# Sheet1.net
KiCad netlist of a schematic drawn in Altium Designer
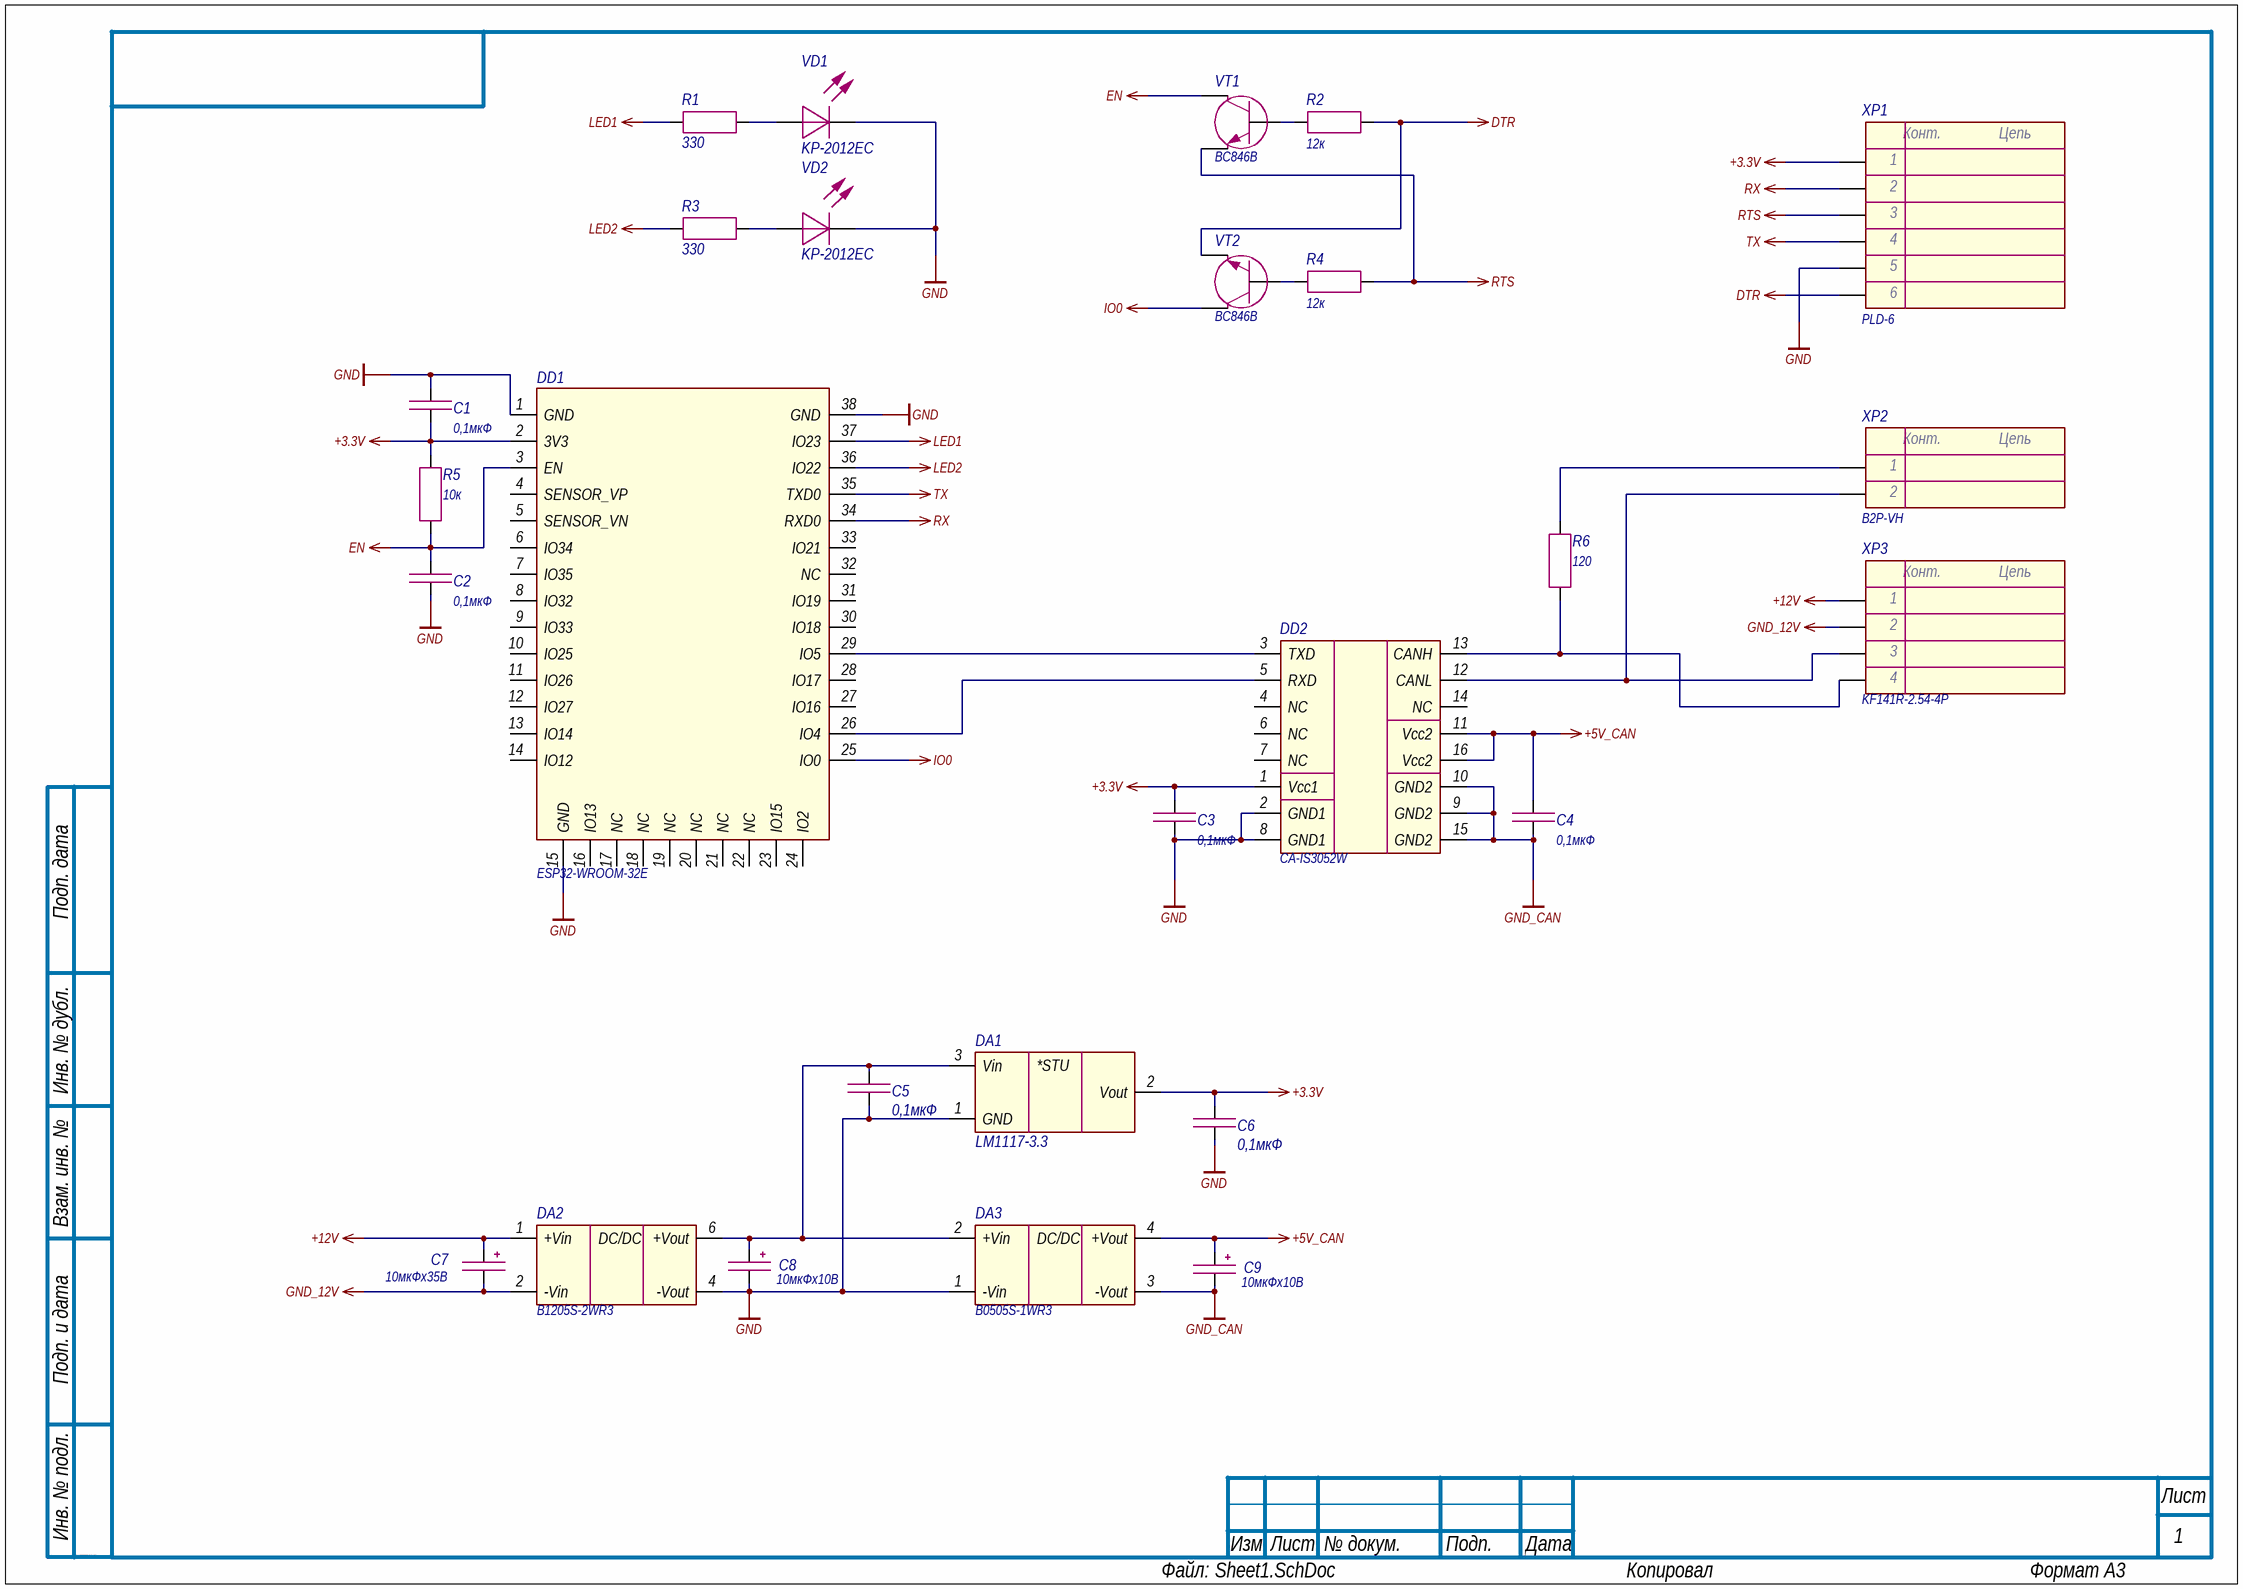
[diagram p0: Sheet1.SchDoc]

(export (version "E")
  (design (tool "Eeschema 10.0.6"))
  (components
    (comp (ref "C1")
      (value "0,1мкФ")
      (footprint "Pcb_library:CAP_0603")
      (fields (field (name "MANUFACTURER") "Murata"))
      (libsource (lib "lib") (part "Capacitor"))
    )
    (comp (ref "C2")
      (value "0,1мкФ")
      (footprint "Pcb_library:CAP_0603")
      (fields (field (name "MANUFACTURER") "Murata"))
      (libsource (lib "lib") (part "Capacitor"))
    )
    (comp (ref "C3")
      (value "0,1мкФ")
      (footprint "Pcb_library:CAP_0603")
      (fields (field (name "MANUFACTURER") "Murata"))
      (libsource (lib "lib") (part "Capacitor"))
    )
    (comp (ref "C4")
      (value "0,1мкФ")
      (footprint "Pcb_library:CAP_0603")
      (fields (field (name "MANUFACTURER") "Murata"))
      (libsource (lib "lib") (part "Capacitor"))
    )
    (comp (ref "C5")
      (value "0,1мкФ")
      (footprint "Pcb_library:CAP_0603")
      (fields (field (name "MANUFACTURER") "Murata"))
      (libsource (lib "lib") (part "Capacitor"))
    )
    (comp (ref "C6")
      (value "0,1мкФ")
      (footprint "Pcb_library:CAP_0603")
      (fields (field (name "MANUFACTURER") "Murata"))
      (libsource (lib "lib") (part "Capacitor"))
    )
    (comp (ref "C7")
      (value "10мкФх35B")
      (footprint "Pcb_library:CAP_C")
      (libsource (lib "Schem_library") (part "Capacitor_Polar"))
    )
    (comp (ref "C8")
      (value "10мкФх10B")
      (footprint "Pcb_library:CAP_A")
      (libsource (lib "Schem_library") (part "Capacitor_Polar"))
    )
    (comp (ref "C9")
      (value "10мкФх10B")
      (footprint "Pcb_library:CAP_A")
      (libsource (lib "Schem_library") (part "Capacitor_Polar"))
    )
    (comp (ref "DA1")
      (value "LM1117-3.3")
      (footprint "Pcb_library:TO-252")
      (fields (field (name "MANUFACTURER") "STMicroelectronics"))
      (libsource (lib "lib") (part "LM1117-3.3"))
    )
    (comp (ref "DA2")
      (value "B1205S-2WR3")
      (footprint "PcbLib1:B1205S2WR3")
      (description "Power Supply")
      (libsource (lib "Schlib1") (part "B1205S-2WR3"))
    )
    (comp (ref "DA3")
      (value "B0505S-1WR3")
      (footprint "B0505S1WR3")
      (description "Power Supply")
      (libsource (lib "Schlib1") (part "B0505S-1WR3"))
    )
    (comp (ref "DD1")
      (value "ESP32-WROOM-32E")
      (footprint "ESP32_WROOM_32E")
      (libsource (lib "lib") (part "ESP32-WROOM-32E"))
    )
    (comp (ref "DD2")
      (value "CA-IS3052W")
      (footprint "SOIC-16W")
      (description "Isolated CAN Transceiver")
      (libsource (lib "lib") (part "CA-IS3052W"))
    )
    (comp (ref "R1")
      (value "330")
      (footprint "Pcb_library:RES_0603")
      (fields (field (name "MANUFACTURER") "Yageo"))
      (libsource (lib "lib") (part "Resistor_6"))
    )
    (comp (ref "R2")
      (value "12к")
      (footprint "Pcb_library:RES_0603")
      (fields (field (name "MANUFACTURER") "Yageo"))
      (libsource (lib "lib") (part "Resistor_14"))
    )
    (comp (ref "R3")
      (value "330")
      (footprint "Pcb_library:RES_0603")
      (fields (field (name "MANUFACTURER") "Yageo"))
      (libsource (lib "lib") (part "Resistor_6"))
    )
    (comp (ref "R4")
      (value "12к")
      (footprint "Pcb_library:RES_0603")
      (fields (field (name "MANUFACTURER") "Yageo"))
      (libsource (lib "lib") (part "Resistor_14"))
    )
    (comp (ref "R5")
      (value "10к")
      (footprint "Pcb_library:RES_0603")
      (fields (field (name "MANUFACTURER") "Yageo"))
      (libsource (lib "lib") (part "Resistor_1"))
    )
    (comp (ref "R6")
      (value "120")
      (footprint "Pcb_library:RES_0805")
      (fields (field (name "MANUFACTURER") "Yageo"))
      (libsource (lib "lib") (part "Resistor_5"))
    )
    (comp (ref "VD1")
      (value "KP-2012EC")
      (footprint "Pcb_library:LED_0805")
      (fields (field (name "MANUFACTURER") "Kingbright"))
      (libsource (lib "lib") (part "LED"))
    )
    (comp (ref "VD2")
      (value "KP-2012EC")
      (footprint "Pcb_library:LED_0805")
      (fields (field (name "MANUFACTURER") "Kingbright"))
      (libsource (lib "lib") (part "LED"))
    )
    (comp (ref "VT1")
      (value "BC846B")
      (footprint "SOT-23-3")
      (description "npn")
      (libsource (lib "lib") (part "BC846B"))
    )
    (comp (ref "VT2")
      (value "BC846B")
      (footprint "SOT-23-3")
      (description "npn")
      (libsource (lib "lib") (part "BC846B"))
    )
    (comp (ref "XP1")
      (value "PLD-6")
      (footprint "Pcb_library:PLD-6")
      (fields (field (name "MANUFACTURER") "Connfly"))
      (libsource (lib "lib") (part "Connector-6"))
    )
    (comp (ref "XP2")
      (value "B2P-VH")
      (footprint "HDR-TH_2P-P2.54-V-M")
      (fields (field (name "MANUFACTURER") "JST"))
      (libsource (lib "lib") (part "Connector-2"))
    )
    (comp (ref "XP3")
      (value "KF141R-2.54-4P")
      (footprint "CONN-TH_4P-P2.54_KF141R-2.54-4P")
      (libsource (lib "Schlib1") (part "KF141R-2.54-4P"))
    )
  )
  (nets
    (net (code "1") (name "+3.3V") (class "Default")
      (node (ref "C1") (pin "1") (pinfunction "1_1") (pintype "passive"))
      (node (ref "C3") (pin "2") (pinfunction "2_2") (pintype "passive"))
      (node (ref "C6") (pin "2") (pinfunction "2_2") (pintype "passive"))
      (node (ref "DA1") (pin "2") (pinfunction "Vout_2") (pintype "passive"))
      (node (ref "DD1") (pin "2") (pinfunction "3V3_2") (pintype "passive"))
      (node (ref "DD2") (pin "1") (pinfunction "Vcc1_1") (pintype "passive"))
      (node (ref "R5") (pin "2") (pinfunction "2_2") (pintype "passive"))
      (node (ref "XP1") (pin "1") (pintype "passive"))
    )
    (net (code "2") (name "+5V_CAN") (class "Default")
      (node (ref "C4") (pin "2") (pinfunction "2_2") (pintype "passive"))
      (node (ref "C9") (pin "1") (pinfunction "1_1") (pintype "passive"))
      (node (ref "DA3") (pin "4") (pinfunction "+Vout_4") (pintype "passive"))
      (node (ref "DD2") (pin "11") (pinfunction "Vcc2_11") (pintype "passive"))
      (node (ref "DD2") (pin "16") (pinfunction "Vcc2_16") (pintype "passive"))
    )
    (net (code "3") (name "+12V") (class "Default")
      (node (ref "C7") (pin "1") (pinfunction "1_1") (pintype "passive"))
      (node (ref "DA2") (pin "1") (pinfunction "+Vin_1") (pintype "passive"))
      (node (ref "XP3") (pin "1") (pintype "passive"))
    )
    (net (code "4") (name "DTR") (class "Default")
      (node (ref "R2") (pin "2") (pinfunction "2_2") (pintype "passive"))
      (node (ref "VT2") (pin "2") (pinfunction "S_2") (pintype "passive"))
      (node (ref "XP1") (pin "6") (pintype "passive"))
    )
    (net (code "5") (name "EN") (class "Default")
      (node (ref "C2") (pin "2") (pinfunction "2_2") (pintype "passive"))
      (node (ref "DD1") (pin "3") (pinfunction "EN_3") (pintype "passive"))
      (node (ref "R5") (pin "1") (pinfunction "1_1") (pintype "passive"))
      (node (ref "VT1") (pin "3") (pinfunction "D_3") (pintype "passive"))
    )
    (net (code "6") (name "GND") (class "Default")
      (node (ref "C1") (pin "2") (pinfunction "2_2") (pintype "passive"))
      (node (ref "C2") (pin "1") (pinfunction "1_1") (pintype "passive"))
      (node (ref "C3") (pin "1") (pinfunction "1_1") (pintype "passive"))
      (node (ref "C5") (pin "1") (pinfunction "1_1") (pintype "passive"))
      (node (ref "C6") (pin "1") (pinfunction "1_1") (pintype "passive"))
      (node (ref "C8") (pin "2") (pinfunction "2_2") (pintype "passive"))
      (node (ref "DA1") (pin "1") (pinfunction "GND_1") (pintype "passive"))
      (node (ref "DA2") (pin "4") (pinfunction "-Vout_4") (pintype "passive"))
      (node (ref "DA3") (pin "1") (pinfunction "-Vin_1") (pintype "passive"))
      (node (ref "DD1") (pin "1") (pinfunction "GND_1") (pintype "passive"))
      (node (ref "DD1") (pin "15") (pinfunction "GND_15") (pintype "passive"))
      (node (ref "DD1") (pin "38") (pinfunction "GND_38") (pintype "passive"))
      (node (ref "DD2") (pin "2") (pinfunction "GND1_2") (pintype "passive"))
      (node (ref "DD2") (pin "8") (pinfunction "GND1_8") (pintype "passive"))
      (node (ref "VD1") (pin "2") (pinfunction "C_2") (pintype "passive"))
      (node (ref "VD2") (pin "2") (pinfunction "C_2") (pintype "passive"))
      (node (ref "XP1") (pin "5") (pintype "passive"))
    )
    (net (code "7") (name "GND_12V") (class "Default")
      (node (ref "C7") (pin "2") (pinfunction "2_2") (pintype "passive"))
      (node (ref "DA2") (pin "2") (pinfunction "-Vin_2") (pintype "passive"))
      (node (ref "XP3") (pin "2") (pintype "passive"))
    )
    (net (code "8") (name "GND_CAN") (class "Default")
      (node (ref "C4") (pin "1") (pinfunction "1_1") (pintype "passive"))
      (node (ref "C9") (pin "2") (pinfunction "2_2") (pintype "passive"))
      (node (ref "DA3") (pin "3") (pinfunction "-Vout_3") (pintype "passive"))
      (node (ref "DD2") (pin "10") (pinfunction "GND2_10") (pintype "passive"))
      (node (ref "DD2") (pin "15") (pinfunction "GND2_15") (pintype "passive"))
      (node (ref "DD2") (pin "9") (pinfunction "GND2_9") (pintype "passive"))
    )
    (net (code "9") (name "IO0") (class "Default")
      (node (ref "DD1") (pin "25") (pinfunction "IO0_25") (pintype "passive"))
      (node (ref "VT2") (pin "3") (pinfunction "D_3") (pintype "passive"))
    )
    (net (code "10") (name "LED1") (class "Default")
      (node (ref "DD1") (pin "37") (pinfunction "IO23_37") (pintype "passive"))
      (node (ref "R1") (pin "1") (pinfunction "1_1") (pintype "passive"))
    )
    (net (code "11") (name "LED2") (class "Default")
      (node (ref "DD1") (pin "36") (pinfunction "IO22_36") (pintype "passive"))
      (node (ref "R3") (pin "1") (pinfunction "1_1") (pintype "passive"))
    )
    (net (code "12") (name "Net-(DA1-Vin)") (class "Default")
      (node (ref "C5") (pin "2") (pinfunction "2_2") (pintype "passive"))
      (node (ref "C8") (pin "1") (pinfunction "1_1") (pintype "passive"))
      (node (ref "DA1") (pin "3") (pinfunction "Vin_3") (pintype "passive"))
      (node (ref "DA2") (pin "6") (pinfunction "+Vout_6") (pintype "passive"))
      (node (ref "DA3") (pin "2") (pinfunction "+Vin_2") (pintype "passive"))
    )
    (net (code "13") (name "Net-(DD1-IO4)") (class "Default")
      (node (ref "DD1") (pin "26") (pinfunction "IO4_26") (pintype "passive"))
      (node (ref "DD2") (pin "5") (pinfunction "RXD_5") (pintype "passive"))
    )
    (net (code "14") (name "Net-(DD1-IO5)") (class "Default")
      (node (ref "DD1") (pin "29") (pinfunction "IO5_29") (pintype "passive"))
      (node (ref "DD2") (pin "3") (pinfunction "TXD_3") (pintype "passive"))
    )
    (net (code "15") (name "Net-(DD2-CANH)") (class "Default")
      (node (ref "DD2") (pin "13") (pinfunction "CANH_13") (pintype "passive"))
      (node (ref "R6") (pin "1") (pinfunction "1_1") (pintype "passive"))
      (node (ref "XP3") (pin "4") (pintype "passive"))
    )
    (net (code "16") (name "Net-(DD2-CANL)") (class "Default")
      (node (ref "DD2") (pin "12") (pinfunction "CANL_12") (pintype "passive"))
      (node (ref "XP2") (pin "2") (pintype "passive"))
      (node (ref "XP3") (pin "3") (pintype "passive"))
    )
    (net (code "17") (name "Net-(R6-Pad2)") (class "Default")
      (node (ref "R6") (pin "2") (pinfunction "2_2") (pintype "passive"))
      (node (ref "XP2") (pin "1") (pintype "passive"))
    )
    (net (code "18") (name "Net-(VD1-A)") (class "Default")
      (node (ref "R1") (pin "2") (pinfunction "2_2") (pintype "passive"))
      (node (ref "VD1") (pin "1") (pinfunction "A_1") (pintype "passive"))
    )
    (net (code "19") (name "Net-(VD2-A)") (class "Default")
      (node (ref "R3") (pin "2") (pinfunction "2_2") (pintype "passive"))
      (node (ref "VD2") (pin "1") (pinfunction "A_1") (pintype "passive"))
    )
    (net (code "20") (name "Net-(VT1-G)") (class "Default")
      (node (ref "R2") (pin "1") (pinfunction "1_1") (pintype "passive"))
      (node (ref "VT1") (pin "1") (pinfunction "G_1") (pintype "passive"))
    )
    (net (code "21") (name "Net-(VT2-G)") (class "Default")
      (node (ref "R4") (pin "1") (pinfunction "1_1") (pintype "passive"))
      (node (ref "VT2") (pin "1") (pinfunction "G_1") (pintype "passive"))
    )
    (net (code "22") (name "RTS") (class "Default")
      (node (ref "R4") (pin "2") (pinfunction "2_2") (pintype "passive"))
      (node (ref "VT1") (pin "2") (pinfunction "S_2") (pintype "passive"))
      (node (ref "XP1") (pin "3") (pintype "passive"))
    )
    (net (code "23") (name "RX") (class "Default")
      (node (ref "DD1") (pin "34") (pinfunction "RXD0_34") (pintype "passive"))
      (node (ref "XP1") (pin "2") (pintype "passive"))
    )
    (net (code "24") (name "TX") (class "Default")
      (node (ref "DD1") (pin "35") (pinfunction "TXD0_35") (pintype "passive"))
      (node (ref "XP1") (pin "4") (pintype "passive"))
    )
    (net (code "25") (name "unconnected-(DD1-IO2-Pad24)") (class "Default")
      (node (ref "DD1") (pin "24") (pinfunction "IO2_24") (pintype "passive"))
    )
    (net (code "26") (name "unconnected-(DD1-IO12-Pad14)") (class "Default")
      (node (ref "DD1") (pin "14") (pinfunction "IO12_14") (pintype "passive"))
    )
    (net (code "27") (name "unconnected-(DD1-IO13-Pad16)") (class "Default")
      (node (ref "DD1") (pin "16") (pinfunction "IO13_16") (pintype "passive"))
    )
    (net (code "28") (name "unconnected-(DD1-IO14-Pad13)") (class "Default")
      (node (ref "DD1") (pin "13") (pinfunction "IO14_13") (pintype "passive"))
    )
    (net (code "29") (name "unconnected-(DD1-IO15-Pad23)") (class "Default")
      (node (ref "DD1") (pin "23") (pinfunction "IO15_23") (pintype "passive"))
    )
    (net (code "30") (name "unconnected-(DD1-IO16-Pad27)") (class "Default")
      (node (ref "DD1") (pin "27") (pinfunction "IO16_27") (pintype "passive"))
    )
    (net (code "31") (name "unconnected-(DD1-IO17-Pad28)") (class "Default")
      (node (ref "DD1") (pin "28") (pinfunction "IO17_28") (pintype "passive"))
    )
    (net (code "32") (name "unconnected-(DD1-IO18-Pad30)") (class "Default")
      (node (ref "DD1") (pin "30") (pinfunction "IO18_30") (pintype "passive"))
    )
    (net (code "33") (name "unconnected-(DD1-IO19-Pad31)") (class "Default")
      (node (ref "DD1") (pin "31") (pinfunction "IO19_31") (pintype "passive"))
    )
    (net (code "34") (name "unconnected-(DD1-IO21-Pad33)") (class "Default")
      (node (ref "DD1") (pin "33") (pinfunction "IO21_33") (pintype "passive"))
    )
    (net (code "35") (name "unconnected-(DD1-IO25-Pad10)") (class "Default")
      (node (ref "DD1") (pin "10") (pinfunction "IO25_10") (pintype "passive"))
    )
    (net (code "36") (name "unconnected-(DD1-IO26-Pad11)") (class "Default")
      (node (ref "DD1") (pin "11") (pinfunction "IO26_11") (pintype "passive"))
    )
    (net (code "37") (name "unconnected-(DD1-IO27-Pad12)") (class "Default")
      (node (ref "DD1") (pin "12") (pinfunction "IO27_12") (pintype "passive"))
    )
    (net (code "38") (name "unconnected-(DD1-IO32-Pad8)") (class "Default")
      (node (ref "DD1") (pin "8") (pinfunction "IO32_8") (pintype "passive"))
    )
    (net (code "39") (name "unconnected-(DD1-IO33-Pad9)") (class "Default")
      (node (ref "DD1") (pin "9") (pinfunction "IO33_9") (pintype "passive"))
    )
    (net (code "40") (name "unconnected-(DD1-IO34-Pad6)") (class "Default")
      (node (ref "DD1") (pin "6") (pinfunction "IO34_6") (pintype "passive"))
    )
    (net (code "41") (name "unconnected-(DD1-IO35-Pad7)") (class "Default")
      (node (ref "DD1") (pin "7") (pinfunction "IO35_7") (pintype "passive"))
    )
    (net (code "42") (name "unconnected-(DD1-NC-Pad17)") (class "Default")
      (node (ref "DD1") (pin "17") (pinfunction "NC_17") (pintype "passive"))
    )
    (net (code "43") (name "unconnected-(DD1-NC-Pad18)") (class "Default")
      (node (ref "DD1") (pin "18") (pinfunction "NC_18") (pintype "passive"))
    )
    (net (code "44") (name "unconnected-(DD1-NC-Pad19)") (class "Default")
      (node (ref "DD1") (pin "19") (pinfunction "NC_19") (pintype "passive"))
    )
    (net (code "45") (name "unconnected-(DD1-NC-Pad20)") (class "Default")
      (node (ref "DD1") (pin "20") (pinfunction "NC_20") (pintype "passive"))
    )
    (net (code "46") (name "unconnected-(DD1-NC-Pad21)") (class "Default")
      (node (ref "DD1") (pin "21") (pinfunction "NC_21") (pintype "passive"))
    )
    (net (code "47") (name "unconnected-(DD1-NC-Pad22)") (class "Default")
      (node (ref "DD1") (pin "22") (pinfunction "NC_22") (pintype "passive"))
    )
    (net (code "48") (name "unconnected-(DD1-NC-Pad32)") (class "Default")
      (node (ref "DD1") (pin "32") (pinfunction "NC_32") (pintype "passive"))
    )
    (net (code "49") (name "unconnected-(DD1-SENSOR_VN-Pad5)") (class "Default")
      (node (ref "DD1") (pin "5") (pinfunction "SENSOR_VN_5") (pintype "passive"))
    )
    (net (code "50") (name "unconnected-(DD1-SENSOR_VP-Pad4)") (class "Default")
      (node (ref "DD1") (pin "4") (pinfunction "SENSOR_VP_4") (pintype "passive"))
    )
    (net (code "51") (name "unconnected-(DD2-NC-Pad4)") (class "Default")
      (node (ref "DD2") (pin "4") (pinfunction "NC_4") (pintype "passive"))
    )
    (net (code "52") (name "unconnected-(DD2-NC-Pad6)") (class "Default")
      (node (ref "DD2") (pin "6") (pinfunction "NC_6") (pintype "passive"))
    )
    (net (code "53") (name "unconnected-(DD2-NC-Pad7)") (class "Default")
      (node (ref "DD2") (pin "7") (pinfunction "NC_7") (pintype "passive"))
    )
    (net (code "54") (name "unconnected-(DD2-NC-Pad14)") (class "Default")
      (node (ref "DD2") (pin "14") (pinfunction "NC_14") (pintype "passive"))
    )
  )
)
